# Trasiente_y_barrido_de_par_metros.net
KiCad netlist of a schematic drawn in Altium Designer
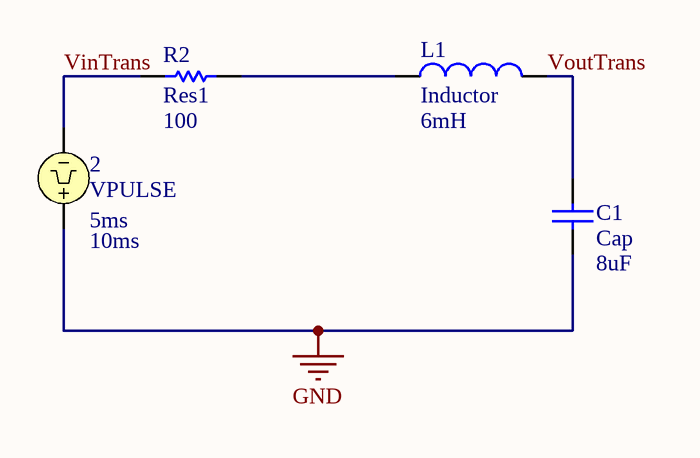
[diagram p0: Trasiente y barrido de parámetros.SchDoc]

(export (version "E")
  (design (tool "Eeschema 10.0.6"))
  (components
    (comp (ref "2")
      (value "VPULSE")
      (description "Pulse Voltage Source")
      (fields
        (field (name "PULSE WIDTH") "5ms")
        (field (name "PERIOD") "10ms")
        (field (name "PUBLISHER") "Altium Limited")
      )
      (libsource (lib "Simulation Sources") (part "VPULSE"))
    )
    (comp (ref "C1")
      (value "Cap")
      (footprint "RAD-0.3")
      (description "Capacitor")
      (fields (field (name "ALTIUM_VALUE") "8uF") (field (name "PUBLISHER") "Altium Limited"))
      (libsource (lib "Miscellaneous Devices") (part "Cap"))
    )
    (comp (ref "L1")
      (value "Inductor")
      (footprint "0402-A")
      (fields (field (name "ALTIUM_VALUE") "6mH") (field (name "PUBLISHER") "Altium Limited"))
      (libsource (lib "Miscellaneous Devices") (part "Inductor"))
    )
    (comp (ref "R2")
      (value "Res1")
      (footprint "AXIAL-0.3")
      (description "Resistor")
      (fields (field (name "ALTIUM_VALUE") "100") (field (name "PUBLISHER") "Altium Limited"))
      (libsource (lib "Miscellaneous Devices") (part "Res1"))
    )
  )
  (nets
    (net (code "1") (name "/VinTrans") (class "Default")
      (node (ref "2") (pin "2") (pinfunction "2_2") (pintype "passive"))
      (node (ref "R2") (pin "1") (pinfunction "1_1") (pintype "passive"))
    )
    (net (code "2") (name "/VoutTrans") (class "Default")
      (node (ref "C1") (pin "2") (pinfunction "2_2") (pintype "passive"))
      (node (ref "L1") (pin "2") (pinfunction "2_2") (pintype "passive"))
    )
    (net (code "3") (name "GND") (class "Default")
      (node (ref "2") (pin "1") (pinfunction "1_1") (pintype "passive"))
      (node (ref "C1") (pin "1") (pinfunction "1_1") (pintype "passive"))
    )
    (net (code "4") (name "Net-(L1-Pad1)") (class "Default")
      (node (ref "L1") (pin "1") (pinfunction "1_1") (pintype "passive"))
      (node (ref "R2") (pin "2") (pinfunction "2_2") (pintype "passive"))
    )
  )
)
